# atarimovie.net
KiCad netlist of a schematic drawn in EAGLE
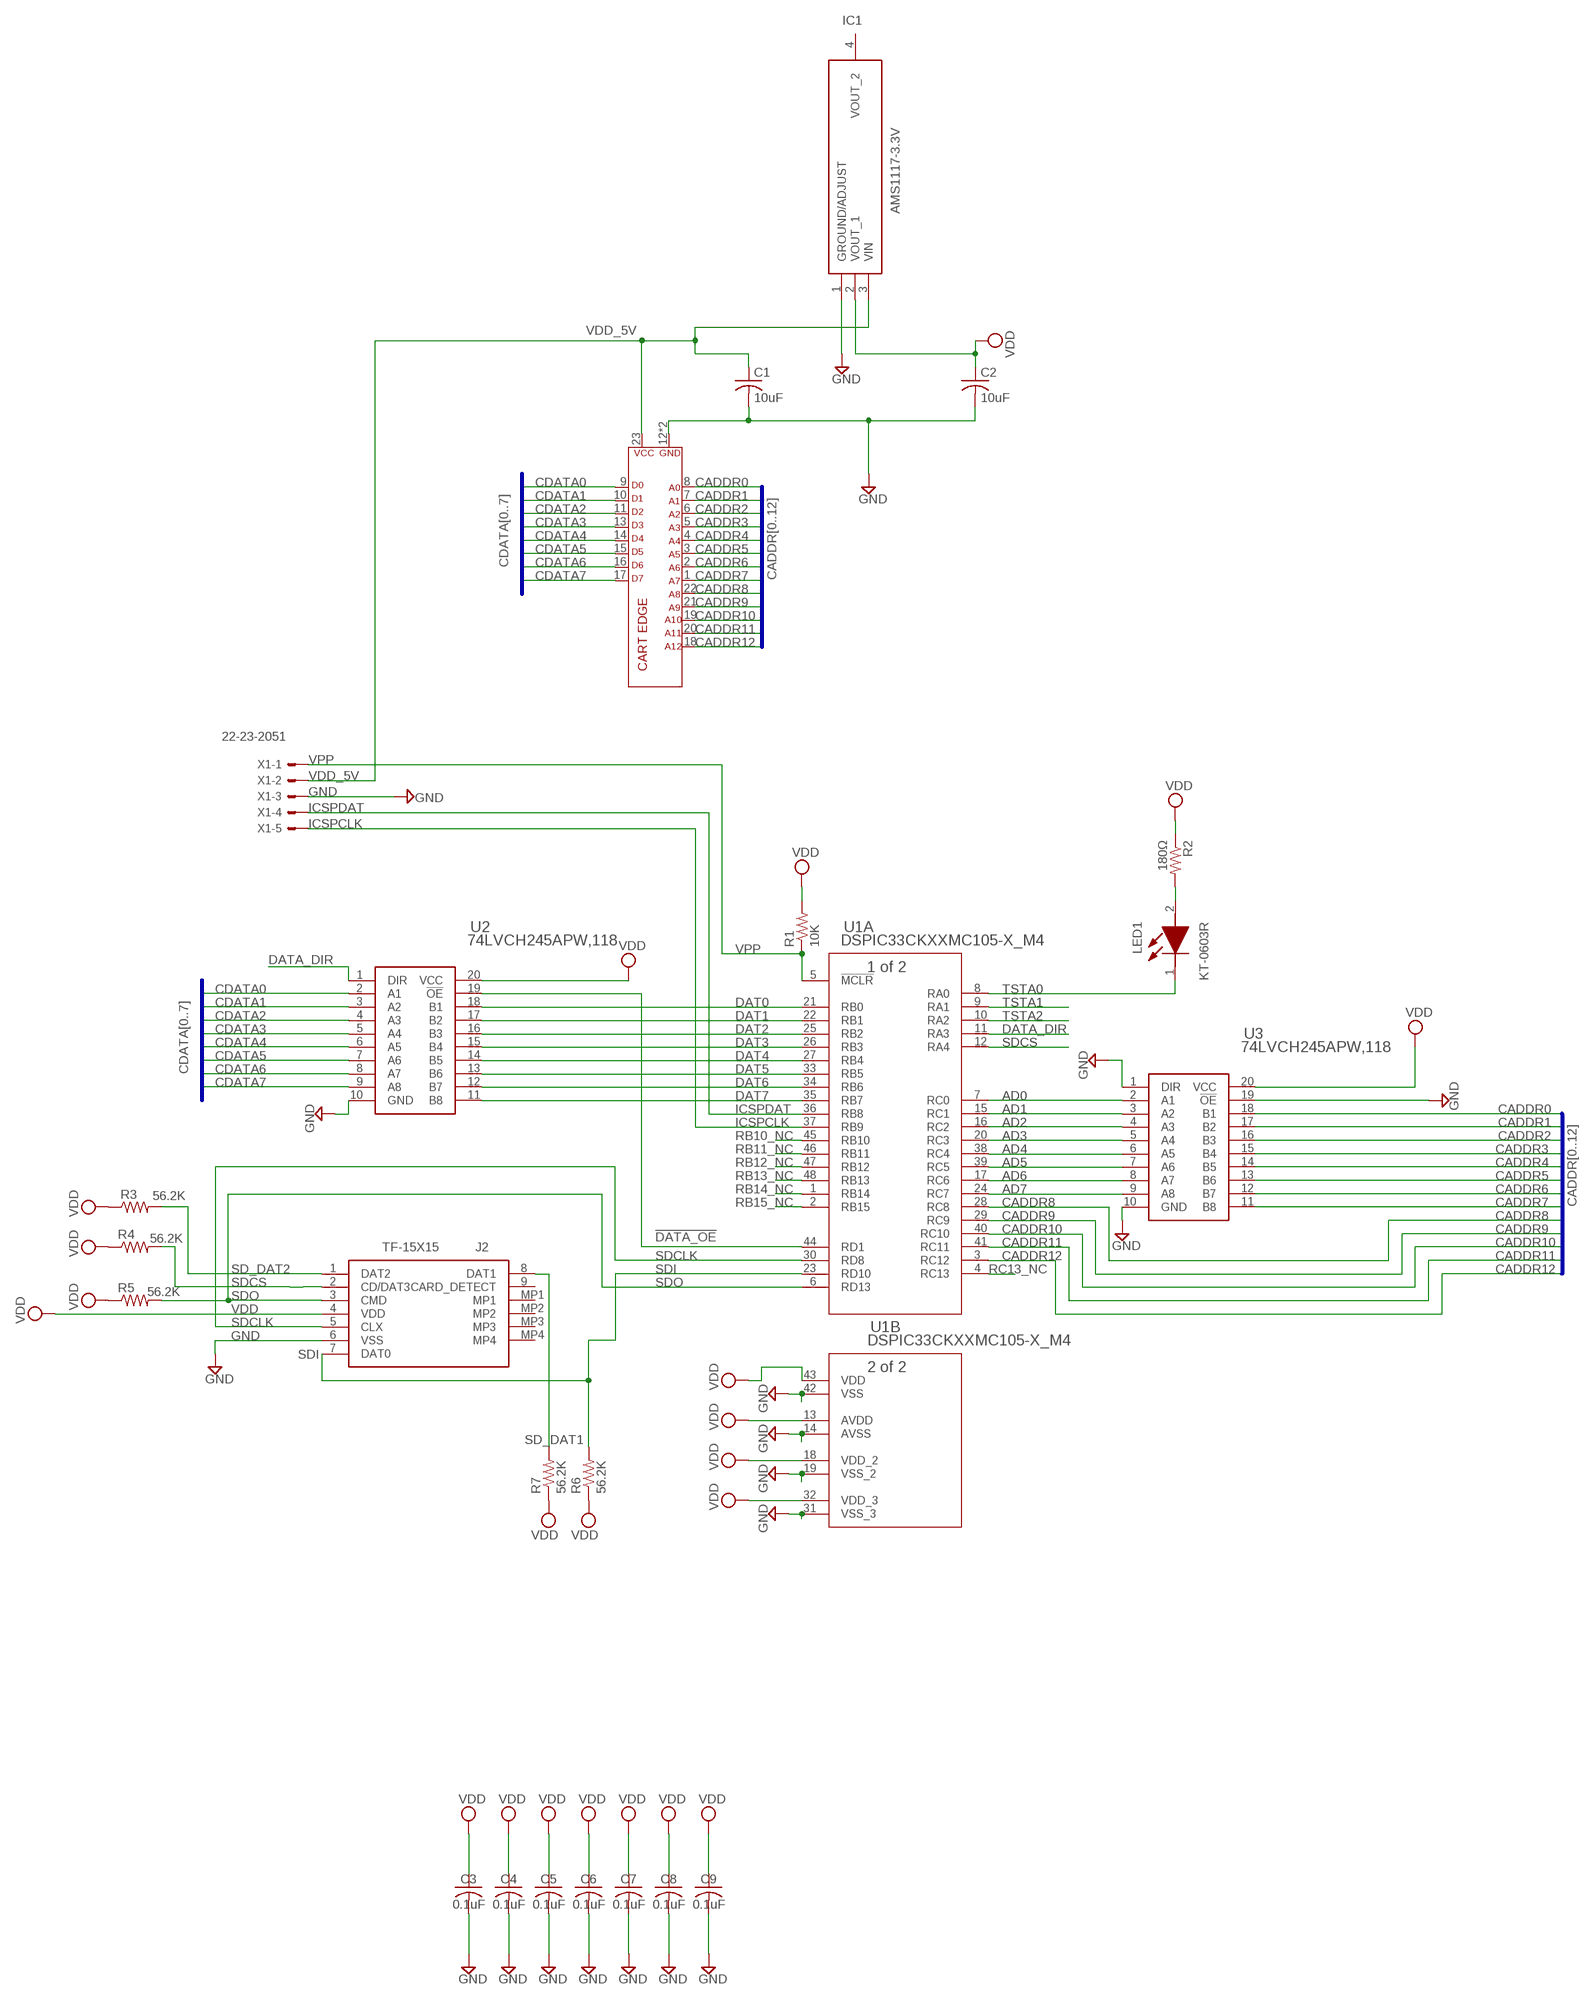
[diagram p0: schematic, sheet 1]

(export (version "E")
  (design (tool "Eeschema 10.0.6"))
  (components
    (comp (ref "C1")
      (value "10uF")
      (footprint "eagle-import:C0603K")
      (libsource (lib "eagle-import") (part "C-USC0603K"))
    )
    (comp (ref "C2")
      (value "10uF")
      (footprint "eagle-import:C0603K")
      (libsource (lib "eagle-import") (part "C-USC0603K"))
    )
    (comp (ref "C3")
      (value "0.1uF")
      (footprint "eagle-import:C0603K")
      (libsource (lib "eagle-import") (part "C-USC0603K"))
    )
    (comp (ref "C4")
      (value "0.1uF")
      (footprint "eagle-import:C0603K")
      (libsource (lib "eagle-import") (part "C-USC0603K"))
    )
    (comp (ref "C5")
      (value "0.1uF")
      (footprint "eagle-import:C0603K")
      (libsource (lib "eagle-import") (part "C-USC0603K"))
    )
    (comp (ref "C6")
      (value "0.1uF")
      (footprint "eagle-import:C0603K")
      (libsource (lib "eagle-import") (part "C-USC0603K"))
    )
    (comp (ref "C7")
      (value "0.1uF")
      (footprint "eagle-import:C0603K")
      (libsource (lib "eagle-import") (part "C-USC0603K"))
    )
    (comp (ref "C8")
      (value "0.1uF")
      (footprint "eagle-import:C0603K")
      (libsource (lib "eagle-import") (part "C-USC0603K"))
    )
    (comp (ref "C9")
      (value "0.1uF")
      (footprint "eagle-import:C0603K")
      (libsource (lib "eagle-import") (part "C-USC0603K"))
    )
    (comp (ref "IC1")
      (value "AMS1117-3.3V")
      (footprint "eagle-import:SOT229P700X180-4N")
      (fields (field (name "MANUFACTURER_PART_NUMBER") "ams1117-3.3v"))
      (libsource (lib "eagle-import") (part "AMS1117-3.3V"))
    )
    (comp (ref "J1")
      (value "CARTRIDGE EDGE")
      (footprint "eagle-import:MED_TABS_SHORT")
      (libsource (lib "eagle-import") (part "ATARI-2600MED_TABS_SHORT"))
    )
    (comp (ref "J2")
      (value "TF-15X15")
      (footprint "eagle-import:TF15X15")
      (libsource (lib "eagle-import") (part "TF-15X15"))
    )
    (comp (ref "LED1")
      (value "KT-0603R")
      (footprint "eagle-import:LEDC1608X70N")
      (libsource (lib "eagle-import") (part "KT-0603R"))
    )
    (comp (ref "R1")
      (value "10K")
      (footprint "eagle-import:R0603")
      (libsource (lib "eagle-import") (part "R-US_R0603"))
    )
    (comp (ref "R2")
      (value "180Ω")
      (footprint "eagle-import:R0603")
      (libsource (lib "eagle-import") (part "R-US_R0603"))
    )
    (comp (ref "R3")
      (value "56.2K")
      (footprint "eagle-import:R0603")
      (libsource (lib "eagle-import") (part "R-US_R0603"))
    )
    (comp (ref "R4")
      (value "56.2K")
      (footprint "eagle-import:R0603")
      (libsource (lib "eagle-import") (part "R-US_R0603"))
    )
    (comp (ref "R5")
      (value "56.2K")
      (footprint "eagle-import:R0603")
      (libsource (lib "eagle-import") (part "R-US_R0603"))
    )
    (comp (ref "R6")
      (value "56.2K")
      (footprint "eagle-import:R0603")
      (libsource (lib "eagle-import") (part "R-US_R0603"))
    )
    (comp (ref "R7")
      (value "56.2K")
      (footprint "eagle-import:R0603")
      (libsource (lib "eagle-import") (part "R-US_R0603"))
    )
    (comp (ref "U1")
      (value "DSPIC33CKXXMC105-X_M4")
      (footprint "eagle-import:UQFN48_6X6MC_MCH")
      (fields
        (field (name "MANUFACTURER_PART_NUMBER") "dsPIC33CKXXMC105-X_M4")
        (field (name "COPYRIGHT") "Copyright (C) 2022 Ultra Librarian. All rights reserved.")
      )
      (libsource (lib "eagle-import") (part "DSPIC33CKXXMC105-X_M4"))
    )
    (comp (ref "U2")
      (value "74LVCH245APW,118")
      (footprint "eagle-import:SOP65P640X110-20N")
      (fields (field (name "MOUSER_PART_NUMBER") "771-74LVCH245APW-T"))
      (libsource (lib "eagle-import") (part "74LVCH245APW,118"))
    )
    (comp (ref "U3")
      (value "74LVCH245APW,118")
      (footprint "eagle-import:SOP65P640X110-20N")
      (fields (field (name "MOUSER_PART_NUMBER") "771-74LVCH245APW-T"))
      (libsource (lib "eagle-import") (part "74LVCH245APW,118"))
    )
    (comp (ref "X1")
      (value "22-23-2051")
      (footprint "eagle-import:22-23-2051")
      (fields (field (name "MF") "MOLEX"))
      (libsource (lib "eagle-import") (part "22-23-2051"))
    )
  )
  (nets
    (net (code "1") (name "/AD0") (class "Default")
      (node (ref "U1") (pin "7") (pinfunction "RC0_7") (pintype "bidirectional"))
      (node (ref "U3") (pin "2") (pinfunction "A1_2") (pintype "bidirectional"))
    )
    (net (code "2") (name "/AD1") (class "Default")
      (node (ref "U1") (pin "15") (pinfunction "RC1_15") (pintype "bidirectional"))
      (node (ref "U3") (pin "3") (pinfunction "A2_3") (pintype "bidirectional"))
    )
    (net (code "3") (name "/AD2") (class "Default")
      (node (ref "U1") (pin "16") (pinfunction "RC2_16") (pintype "bidirectional"))
      (node (ref "U3") (pin "4") (pinfunction "A3_4") (pintype "bidirectional"))
    )
    (net (code "4") (name "/AD3") (class "Default")
      (node (ref "U1") (pin "20") (pinfunction "RC3_20") (pintype "bidirectional"))
      (node (ref "U3") (pin "5") (pinfunction "A4_5") (pintype "bidirectional"))
    )
    (net (code "5") (name "/AD4") (class "Default")
      (node (ref "U1") (pin "38") (pinfunction "RC4_38") (pintype "bidirectional"))
      (node (ref "U3") (pin "6") (pinfunction "A5_6") (pintype "bidirectional"))
    )
    (net (code "6") (name "/AD5") (class "Default")
      (node (ref "U1") (pin "39") (pinfunction "RC5_39") (pintype "bidirectional"))
      (node (ref "U3") (pin "7") (pinfunction "A6_7") (pintype "bidirectional"))
    )
    (net (code "7") (name "/AD6") (class "Default")
      (node (ref "U1") (pin "17") (pinfunction "RC6_17") (pintype "bidirectional"))
      (node (ref "U3") (pin "8") (pinfunction "A7_8") (pintype "bidirectional"))
    )
    (net (code "8") (name "/AD7") (class "Default")
      (node (ref "U1") (pin "24") (pinfunction "RC7_24") (pintype "bidirectional"))
      (node (ref "U3") (pin "9") (pinfunction "A8_9") (pintype "bidirectional"))
    )
    (net (code "9") (name "/CADDR0") (class "Default")
      (node (ref "J1") (pin "8") (pinfunction "A0_8") (pintype "bidirectional"))
      (node (ref "U3") (pin "18") (pinfunction "B1_18") (pintype "bidirectional"))
    )
    (net (code "10") (name "/CADDR1") (class "Default")
      (node (ref "J1") (pin "7") (pinfunction "A1_7") (pintype "bidirectional"))
      (node (ref "U3") (pin "17") (pinfunction "B2_17") (pintype "bidirectional"))
    )
    (net (code "11") (name "/CADDR2") (class "Default")
      (node (ref "J1") (pin "6") (pinfunction "A2_6") (pintype "bidirectional"))
      (node (ref "U3") (pin "16") (pinfunction "B3_16") (pintype "bidirectional"))
    )
    (net (code "12") (name "/CADDR3") (class "Default")
      (node (ref "J1") (pin "5") (pinfunction "A3_5") (pintype "bidirectional"))
      (node (ref "U3") (pin "15") (pinfunction "B4_15") (pintype "bidirectional"))
    )
    (net (code "13") (name "/CADDR4") (class "Default")
      (node (ref "J1") (pin "4") (pinfunction "A4_4") (pintype "bidirectional"))
      (node (ref "U3") (pin "14") (pinfunction "B5_14") (pintype "bidirectional"))
    )
    (net (code "14") (name "/CADDR5") (class "Default")
      (node (ref "J1") (pin "3") (pinfunction "A5_3") (pintype "bidirectional"))
      (node (ref "U3") (pin "13") (pinfunction "B6_13") (pintype "bidirectional"))
    )
    (net (code "15") (name "/CADDR6") (class "Default")
      (node (ref "J1") (pin "2") (pinfunction "A6_2") (pintype "bidirectional"))
      (node (ref "U3") (pin "12") (pinfunction "B7_12") (pintype "bidirectional"))
    )
    (net (code "16") (name "/CADDR7") (class "Default")
      (node (ref "J1") (pin "1") (pinfunction "A7_1") (pintype "bidirectional"))
      (node (ref "U3") (pin "11") (pinfunction "B8_11") (pintype "bidirectional"))
    )
    (net (code "17") (name "/CADDR8") (class "Default")
      (node (ref "J1") (pin "22") (pinfunction "A8_22") (pintype "bidirectional"))
      (node (ref "U1") (pin "28") (pinfunction "RC8_28") (pintype "bidirectional"))
    )
    (net (code "18") (name "/CADDR9") (class "Default")
      (node (ref "J1") (pin "21") (pinfunction "A9_21") (pintype "bidirectional"))
      (node (ref "U1") (pin "29") (pinfunction "RC9_29") (pintype "bidirectional"))
    )
    (net (code "19") (name "/CADDR10") (class "Default")
      (node (ref "J1") (pin "19") (pinfunction "A10_19") (pintype "bidirectional"))
      (node (ref "U1") (pin "40") (pinfunction "RC10_40") (pintype "bidirectional"))
    )
    (net (code "20") (name "/CADDR11") (class "Default")
      (node (ref "J1") (pin "20") (pinfunction "A11_20") (pintype "bidirectional"))
      (node (ref "U1") (pin "41") (pinfunction "RC11_41") (pintype "bidirectional"))
    )
    (net (code "21") (name "/CADDR12") (class "Default")
      (node (ref "J1") (pin "18") (pinfunction "A12_18") (pintype "bidirectional"))
      (node (ref "U1") (pin "3") (pinfunction "RC12_3") (pintype "bidirectional"))
    )
    (net (code "23") (name "/CDATA0") (class "Default")
      (node (ref "J1") (pin "9") (pinfunction "D0_9") (pintype "bidirectional"))
      (node (ref "U2") (pin "2") (pinfunction "A1_2") (pintype "bidirectional"))
    )
    (net (code "24") (name "/CDATA1") (class "Default")
      (node (ref "J1") (pin "10") (pinfunction "D1_10") (pintype "bidirectional"))
      (node (ref "U2") (pin "3") (pinfunction "A2_3") (pintype "bidirectional"))
    )
    (net (code "25") (name "/CDATA2") (class "Default")
      (node (ref "J1") (pin "11") (pinfunction "D2_11") (pintype "bidirectional"))
      (node (ref "U2") (pin "4") (pinfunction "A3_4") (pintype "bidirectional"))
    )
    (net (code "26") (name "/CDATA3") (class "Default")
      (node (ref "J1") (pin "13") (pinfunction "D3_13") (pintype "bidirectional"))
      (node (ref "U2") (pin "5") (pinfunction "A4_5") (pintype "bidirectional"))
    )
    (net (code "27") (name "/CDATA4") (class "Default")
      (node (ref "J1") (pin "14") (pinfunction "D4_14") (pintype "bidirectional"))
      (node (ref "U2") (pin "6") (pinfunction "A5_6") (pintype "bidirectional"))
    )
    (net (code "28") (name "/CDATA5") (class "Default")
      (node (ref "J1") (pin "15") (pinfunction "D5_15") (pintype "bidirectional"))
      (node (ref "U2") (pin "7") (pinfunction "A6_7") (pintype "bidirectional"))
    )
    (net (code "29") (name "/CDATA6") (class "Default")
      (node (ref "J1") (pin "16") (pinfunction "D6_16") (pintype "bidirectional"))
      (node (ref "U2") (pin "8") (pinfunction "A7_8") (pintype "bidirectional"))
    )
    (net (code "30") (name "/CDATA7") (class "Default")
      (node (ref "J1") (pin "17") (pinfunction "D7_17") (pintype "bidirectional"))
      (node (ref "U2") (pin "9") (pinfunction "A8_9") (pintype "bidirectional"))
    )
    (net (code "32") (name "/DAT0") (class "Default")
      (node (ref "U1") (pin "21") (pinfunction "RB0_21") (pintype "bidirectional"))
      (node (ref "U2") (pin "18") (pinfunction "B1_18") (pintype "bidirectional"))
    )
    (net (code "33") (name "/DAT1") (class "Default")
      (node (ref "U1") (pin "22") (pinfunction "RB1_22") (pintype "bidirectional"))
      (node (ref "U2") (pin "17") (pinfunction "B2_17") (pintype "bidirectional"))
    )
    (net (code "34") (name "/DAT2") (class "Default")
      (node (ref "U1") (pin "25") (pinfunction "RB2_25") (pintype "bidirectional"))
      (node (ref "U2") (pin "16") (pinfunction "B3_16") (pintype "bidirectional"))
    )
    (net (code "35") (name "/DAT3") (class "Default")
      (node (ref "U1") (pin "26") (pinfunction "RB3_26") (pintype "bidirectional"))
      (node (ref "U2") (pin "15") (pinfunction "B4_15") (pintype "bidirectional"))
    )
    (net (code "36") (name "/DAT4") (class "Default")
      (node (ref "U1") (pin "27") (pinfunction "RB4_27") (pintype "bidirectional"))
      (node (ref "U2") (pin "14") (pinfunction "B5_14") (pintype "bidirectional"))
    )
    (net (code "37") (name "/DAT5") (class "Default")
      (node (ref "U1") (pin "33") (pinfunction "RB5_33") (pintype "bidirectional"))
      (node (ref "U2") (pin "13") (pinfunction "B6_13") (pintype "bidirectional"))
    )
    (net (code "38") (name "/DAT6") (class "Default")
      (node (ref "U1") (pin "34") (pinfunction "RB6_34") (pintype "bidirectional"))
      (node (ref "U2") (pin "12") (pinfunction "B7_12") (pintype "bidirectional"))
    )
    (net (code "39") (name "/DAT7") (class "Default")
      (node (ref "U1") (pin "35") (pinfunction "RB7_35") (pintype "bidirectional"))
      (node (ref "U2") (pin "11") (pinfunction "B8_11") (pintype "bidirectional"))
    )
    (net (code "40") (name "/DATA_DIR") (class "Default")
      (node (ref "U1") (pin "11") (pinfunction "RA3_11") (pintype "bidirectional"))
      (node (ref "U2") (pin "1") (pinfunction "DIR_1") (pintype "bidirectional"))
    )
    (net (code "41") (name "/ICSPCLK") (class "Default")
      (node (ref "U1") (pin "37") (pinfunction "RB9_37") (pintype "bidirectional"))
      (node (ref "X1") (pin "5") (pinfunction "S_5") (pintype "passive"))
    )
    (net (code "42") (name "/ICSPDAT") (class "Default")
      (node (ref "U1") (pin "36") (pinfunction "RB8_36") (pintype "bidirectional"))
      (node (ref "X1") (pin "4") (pinfunction "S_4") (pintype "passive"))
    )
    (net (code "43") (name "/RB10_NC") (class "Default")
      (node (ref "U1") (pin "45") (pinfunction "RB10_45") (pintype "bidirectional"))
    )
    (net (code "44") (name "/RB11_NC") (class "Default")
      (node (ref "U1") (pin "46") (pinfunction "RB11_46") (pintype "bidirectional"))
    )
    (net (code "45") (name "/RB12_NC") (class "Default")
      (node (ref "U1") (pin "47") (pinfunction "RB12_47") (pintype "bidirectional"))
    )
    (net (code "46") (name "/RB13_NC") (class "Default")
      (node (ref "U1") (pin "48") (pinfunction "RB13_48") (pintype "bidirectional"))
    )
    (net (code "47") (name "/RB14_NC") (class "Default")
      (node (ref "U1") (pin "1") (pinfunction "RB14_1") (pintype "bidirectional"))
    )
    (net (code "48") (name "/RB15_NC") (class "Default")
      (node (ref "U1") (pin "2") (pinfunction "RB15_2") (pintype "bidirectional"))
    )
    (net (code "49") (name "/RC13_NC") (class "Default")
      (node (ref "U1") (pin "4") (pinfunction "RC13_4") (pintype "bidirectional"))
    )
    (net (code "50") (name "/SDCLK") (class "Default")
      (node (ref "J2") (pin "5") (pinfunction "CLX_5") (pintype "bidirectional"))
      (node (ref "U1") (pin "30") (pinfunction "RD8_30") (pintype "bidirectional"))
    )
    (net (code "51") (name "/SDCS") (class "Default")
      (node (ref "J2") (pin "2") (pinfunction "CD/DAT3_2") (pintype "bidirectional"))
      (node (ref "R4") (pin "2") (pinfunction "2_2") (pintype "passive"))
      (node (ref "U1") (pin "12") (pinfunction "RA4_12") (pintype "bidirectional"))
    )
    (net (code "52") (name "/SDI") (class "Default")
      (node (ref "J2") (pin "7") (pinfunction "DAT0_7") (pintype "bidirectional"))
      (node (ref "R6") (pin "2") (pinfunction "2_2") (pintype "passive"))
      (node (ref "U1") (pin "23") (pinfunction "RD10_23") (pintype "bidirectional"))
    )
    (net (code "53") (name "/SDO") (class "Default")
      (node (ref "J2") (pin "3") (pinfunction "CMD_3") (pintype "bidirectional"))
      (node (ref "R5") (pin "2") (pinfunction "2_2") (pintype "passive"))
      (node (ref "U1") (pin "6") (pinfunction "RD13_6") (pintype "bidirectional"))
    )
    (net (code "54") (name "/SD_DAT1") (class "Default")
      (node (ref "J2") (pin "8") (pinfunction "DAT1_8") (pintype "bidirectional"))
      (node (ref "R7") (pin "2") (pinfunction "2_2") (pintype "passive"))
    )
    (net (code "55") (name "/SD_DAT2") (class "Default")
      (node (ref "J2") (pin "1") (pinfunction "DAT2_1") (pintype "bidirectional"))
      (node (ref "R3") (pin "2") (pinfunction "2_2") (pintype "passive"))
    )
    (net (code "56") (name "/TSTA0") (class "Default")
      (node (ref "LED1") (pin "1") (pinfunction "K_1") (pintype "bidirectional"))
      (node (ref "U1") (pin "8") (pinfunction "RA0_8") (pintype "bidirectional"))
    )
    (net (code "57") (name "/TSTA1") (class "Default")
      (node (ref "U1") (pin "9") (pinfunction "RA1_9") (pintype "bidirectional"))
    )
    (net (code "58") (name "/TSTA2") (class "Default")
      (node (ref "U1") (pin "10") (pinfunction "RA2_10") (pintype "bidirectional"))
    )
    (net (code "59") (name "/VDD_5V") (class "Default")
      (node (ref "C1") (pin "1") (pinfunction "1_1") (pintype "passive"))
      (node (ref "IC1") (pin "3") (pinfunction "VIN_3") (pintype "bidirectional"))
      (node (ref "J1") (pin "23") (pinfunction "VCC_23") (pintype "power_in"))
      (node (ref "X1") (pin "2") (pinfunction "S_2") (pintype "passive"))
    )
    (net (code "60") (name "/VPP") (class "Default")
      (node (ref "R1") (pin "1") (pinfunction "1_1") (pintype "passive"))
      (node (ref "U1") (pin "5") (pinfunction "~{MCLR}_5") (pintype "input"))
      (node (ref "X1") (pin "1") (pinfunction "S_1") (pintype "passive"))
    )
    (net (code "61") (name "/~{DATA_OE}") (class "Default")
      (node (ref "U1") (pin "44") (pinfunction "RD1_44") (pintype "bidirectional"))
      (node (ref "U2") (pin "19") (pinfunction "~{OE}_19") (pintype "bidirectional"))
    )
    (net (code "62") (name "GND") (class "Default")
      (node (ref "C1") (pin "2") (pinfunction "2_2") (pintype "passive"))
      (node (ref "C2") (pin "2") (pinfunction "2_2") (pintype "passive"))
      (node (ref "C3") (pin "2") (pinfunction "2_2") (pintype "passive"))
      (node (ref "C4") (pin "2") (pinfunction "2_2") (pintype "passive"))
      (node (ref "C5") (pin "2") (pinfunction "2_2") (pintype "passive"))
      (node (ref "C6") (pin "2") (pinfunction "2_2") (pintype "passive"))
      (node (ref "C7") (pin "2") (pinfunction "2_2") (pintype "passive"))
      (node (ref "C8") (pin "2") (pinfunction "2_2") (pintype "passive"))
      (node (ref "C9") (pin "2") (pinfunction "2_2") (pintype "passive"))
      (node (ref "IC1") (pin "1") (pinfunction "GROUND/ADJUST_1") (pintype "bidirectional"))
      (node (ref "J1") (pin "12") (pinfunction "GND_12") (pintype "power_in"))
      (node (ref "J1") (pin "24") (pinfunction "GND_24") (pintype "power_in"))
      (node (ref "J2") (pin "6") (pinfunction "VSS_6") (pintype "bidirectional"))
      (node (ref "U1") (pin "14") (pinfunction "AVSS_14") (pintype "power_in"))
      (node (ref "U1") (pin "19") (pinfunction "VSS_2_19") (pintype "power_in"))
      (node (ref "U1") (pin "31") (pinfunction "VSS_3_31") (pintype "power_in"))
      (node (ref "U1") (pin "42") (pinfunction "VSS_42") (pintype "power_in"))
      (node (ref "U2") (pin "10") (pinfunction "GND_10") (pintype "bidirectional"))
      (node (ref "U3") (pin "1") (pinfunction "DIR_1") (pintype "bidirectional"))
      (node (ref "U3") (pin "10") (pinfunction "GND_10") (pintype "bidirectional"))
      (node (ref "U3") (pin "19") (pinfunction "~{OE}_19") (pintype "bidirectional"))
      (node (ref "X1") (pin "3") (pinfunction "S_3") (pintype "passive"))
    )
    (net (code "63") (name "Net-(LED1-A)") (class "Default")
      (node (ref "LED1") (pin "2") (pinfunction "A_2") (pintype "bidirectional"))
      (node (ref "R2") (pin "2") (pinfunction "2_2") (pintype "passive"))
    )
    (net (code "64") (name "VDD") (class "Default")
      (node (ref "C2") (pin "1") (pinfunction "1_1") (pintype "passive"))
      (node (ref "C3") (pin "1") (pinfunction "1_1") (pintype "passive"))
      (node (ref "C4") (pin "1") (pinfunction "1_1") (pintype "passive"))
      (node (ref "C5") (pin "1") (pinfunction "1_1") (pintype "passive"))
      (node (ref "C6") (pin "1") (pinfunction "1_1") (pintype "passive"))
      (node (ref "C7") (pin "1") (pinfunction "1_1") (pintype "passive"))
      (node (ref "C8") (pin "1") (pinfunction "1_1") (pintype "passive"))
      (node (ref "C9") (pin "1") (pinfunction "1_1") (pintype "passive"))
      (node (ref "IC1") (pin "2") (pinfunction "VOUT_1_2") (pintype "bidirectional"))
      (node (ref "J2") (pin "4") (pinfunction "VDD_4") (pintype "bidirectional"))
      (node (ref "R1") (pin "2") (pinfunction "2_2") (pintype "passive"))
      (node (ref "R2") (pin "1") (pinfunction "1_1") (pintype "passive"))
      (node (ref "R3") (pin "1") (pinfunction "1_1") (pintype "passive"))
      (node (ref "R4") (pin "1") (pinfunction "1_1") (pintype "passive"))
      (node (ref "R5") (pin "1") (pinfunction "1_1") (pintype "passive"))
      (node (ref "R6") (pin "1") (pinfunction "1_1") (pintype "passive"))
      (node (ref "R7") (pin "1") (pinfunction "1_1") (pintype "passive"))
      (node (ref "U1") (pin "13") (pinfunction "AVDD_13") (pintype "power_in"))
      (node (ref "U1") (pin "18") (pinfunction "VDD_2_18") (pintype "power_in"))
      (node (ref "U1") (pin "32") (pinfunction "VDD_3_32") (pintype "power_in"))
      (node (ref "U1") (pin "43") (pinfunction "VDD_43") (pintype "power_in"))
      (node (ref "U2") (pin "20") (pinfunction "VCC_20") (pintype "bidirectional"))
      (node (ref "U3") (pin "20") (pinfunction "VCC_20") (pintype "bidirectional"))
    )
    (net (code "65") (name "unconnected-(IC1-VOUT_2-Pad4)") (class "Default")
      (node (ref "IC1") (pin "4") (pinfunction "VOUT_2_4") (pintype "bidirectional"))
    )
    (net (code "66") (name "unconnected-(J2-CARD_DETECT-Pad9)") (class "Default")
      (node (ref "J2") (pin "9") (pinfunction "CARD_DETECT_9") (pintype "bidirectional"))
    )
    (net (code "67") (name "unconnected-(J2-PadMP1)") (class "Default")
      (node (ref "J2") (pin "MP1") (pinfunction "MP1_MP1") (pintype "bidirectional"))
    )
    (net (code "68") (name "unconnected-(J2-PadMP2)") (class "Default")
      (node (ref "J2") (pin "MP2") (pinfunction "MP2_MP2") (pintype "bidirectional"))
    )
    (net (code "69") (name "unconnected-(J2-PadMP3)") (class "Default")
      (node (ref "J2") (pin "MP3") (pinfunction "MP3_MP3") (pintype "bidirectional"))
    )
    (net (code "70") (name "unconnected-(J2-PadMP4)") (class "Default")
      (node (ref "J2") (pin "MP4") (pinfunction "MP4_MP4") (pintype "bidirectional"))
    )
  )
)
